# Sheet1.net
KiCad netlist of a schematic drawn in Altium Designer
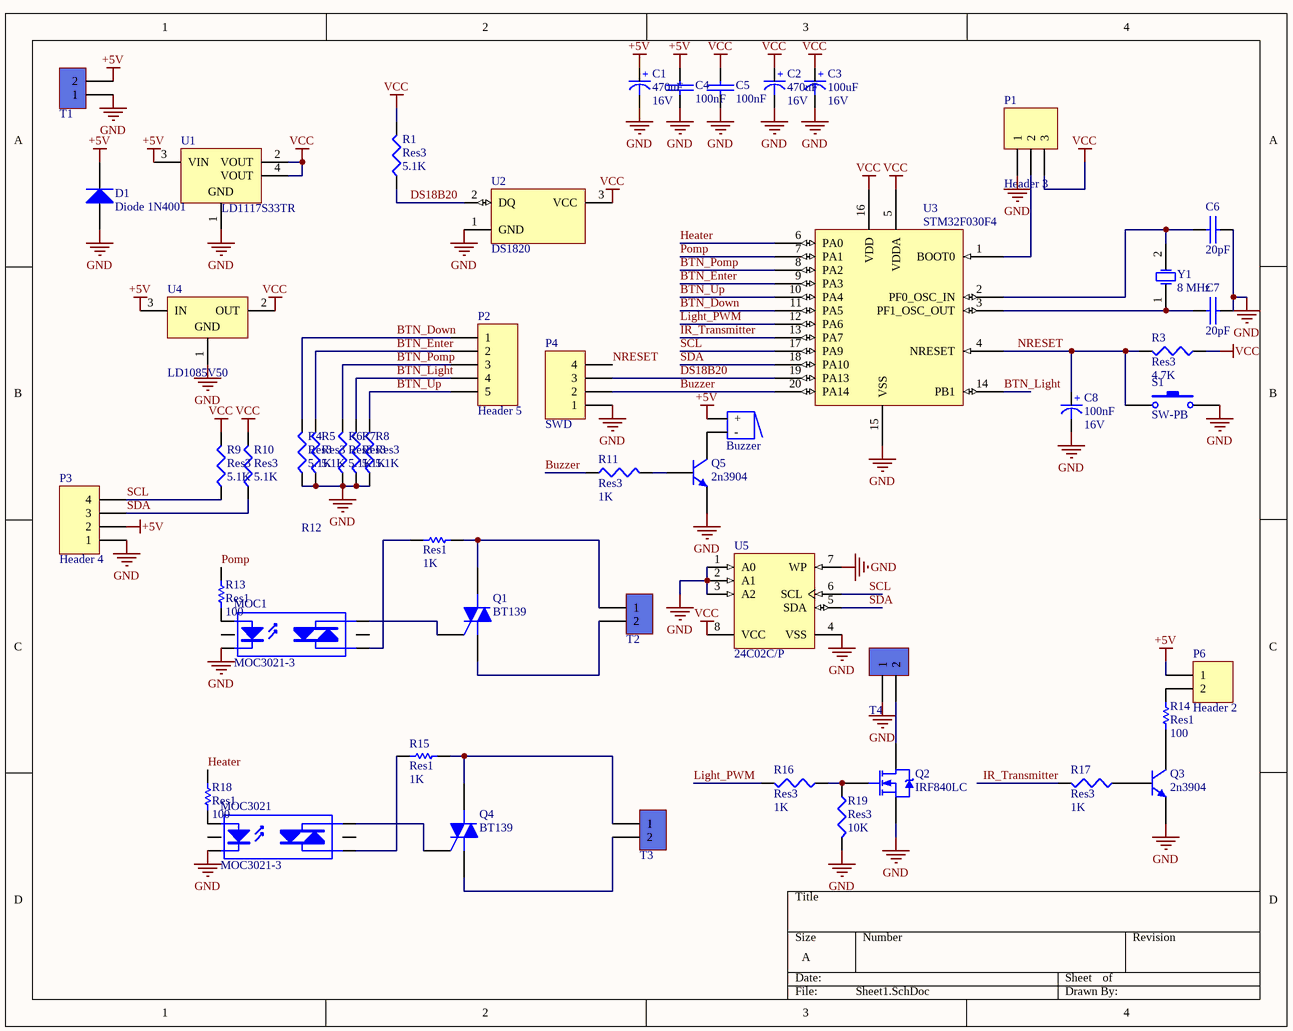
[diagram p0: Sheet1.SchDoc]

(export (version "E")
  (design (tool "Eeschema 10.0.6"))
  (components
    (comp (ref "Buzzer")
      (value "Buzzer")
      (footprint "BUZZER")
      (fields (field (name "DESIGNER") "Seyed Mohsen Ghasemain"))
      (libsource (lib "PicPars.com_usefully_Library") (part "Buzzer"))
    )
    (comp (ref "C1")
      (value "470uF")
      (footprint "cap 03")
      (description "Polar Capacitor")
      (fields (field (name "VOLTAGE") "16V") (field (name "DESIGNER") "Saeid Jorablo"))
      (libsource (lib "My_Library") (part "Cap-Polar"))
    )
    (comp (ref "C2")
      (value "470uF")
      (footprint "cap 03")
      (description "Polar Capacitor")
      (fields (field (name "VOLTAGE") "16V") (field (name "DESIGNER") "Saeid Jorablo"))
      (libsource (lib "My_Library") (part "Cap-Polar"))
    )
    (comp (ref "C3")
      (value "100uF")
      (footprint "cap 02")
      (description "Polar Capacitor")
      (fields (field (name "VOLTAGE") "16V") (field (name "DESIGNER") "Saeid Jorablo"))
      (libsource (lib "My_Library") (part "Cap-Polar"))
    )
    (comp (ref "C4")
      (value "100nF")
      (footprint "SMD_CAP_1206")
      (description "Bipolar Capacitor")
      (fields (field (name "VOLTAGE") "100V") (field (name "DESIGNER") "Saeid Jorablo"))
      (libsource (lib "My_Library") (part "Cap-Bipolar"))
    )
    (comp (ref "C5")
      (value "100nF")
      (footprint "SMD_CAP_1206")
      (description "Bipolar Capacitor")
      (fields (field (name "VOLTAGE") "100V") (field (name "DESIGNER") "Saeid Jorablo"))
      (libsource (lib "My_Library") (part "Cap-Bipolar"))
    )
    (comp (ref "C6")
      (value "20pF")
      (footprint "SMD_CAP_0603")
      (description "Bipolar Capacitor")
      (fields (field (name "VOLTAGE") "100V") (field (name "DESIGNER") "Saeid Jorablo"))
      (libsource (lib "My_Library") (part "Cap-Bipolar"))
    )
    (comp (ref "C7")
      (value "20pF")
      (footprint "SMD_CAP_0603")
      (description "Bipolar Capacitor")
      (fields (field (name "VOLTAGE") "100V") (field (name "DESIGNER") "Saeid Jorablo"))
      (libsource (lib "My_Library") (part "Cap-Bipolar"))
    )
    (comp (ref "C8")
      (value "100nF")
      (footprint "cap 01")
      (description "Polar Capacitor")
      (fields (field (name "VOLTAGE") "16V") (field (name "DESIGNER") "Saeid Jorablo"))
      (libsource (lib "My_Library") (part "Cap-Polar"))
    )
    (comp (ref "D1")
      (value "Diode 1N4001")
      (footprint "DO-41")
      (description "1 Amp General Purpose Rectifier")
      (fields (field (name "PUBLISHER") "Altium Limited"))
      (libsource (lib "Miscellaneous Devices") (part "Diode 1N4001"))
    )
    (comp (ref "MOC1")
      (value "MOC3021-3")
      (footprint "DIP-6")
      (description "Opto-Triac")
      (fields
        (field (name "PUBLISHER") "www.picpars.com")
        (field (name "DESIGNER") "Seyed Mohsen Ghasemian")
        (field (name "E-MAIL") "picpars@gmail.com")
      )
      (libsource (lib "usefully_Library") (part "MOC3021-3"))
    )
    (comp (ref "MOC3021")
      (value "MOC3021-3")
      (footprint "DIP-6")
      (description "Opto-Triac")
      (fields
        (field (name "PUBLISHER") "www.picpars.com")
        (field (name "DESIGNER") "Seyed Mohsen Ghasemian")
        (field (name "E-MAIL") "picpars@gmail.com")
      )
      (libsource (lib "usefully_Library") (part "MOC3021-3"))
    )
    (comp (ref "P1")
      (value "Header 3")
      (footprint "HDR1X3")
      (description "Header, 3-Pin")
      (fields (field (name "PUBLISHER") "Altium Limited"))
      (libsource (lib "Miscellaneous Connectors") (part "Header 3"))
    )
    (comp (ref "P2")
      (value "Header 5")
      (footprint "HDR1X5")
      (description "Header, 5-Pin")
      (fields (field (name "PUBLISHER") "Altium Limited"))
      (libsource (lib "Miscellaneous Connectors") (part "Header 5"))
    )
    (comp (ref "P3")
      (value "Header 4")
      (footprint "HDR1X4")
      (description "Header, 4-Pin")
      (fields (field (name "PUBLISHER") "Altium Limited"))
      (libsource (lib "Miscellaneous Connectors") (part "Header 4"))
    )
    (comp (ref "P4")
      (value "SWD")
      (footprint "HDR1X4")
      (description "Header, 4-Pin")
      (fields (field (name "PUBLISHER") "Altium Limited"))
      (libsource (lib "Miscellaneous Connectors") (part "Header 4"))
    )
    (comp (ref "P6")
      (value "Header 2")
      (footprint "HDR1X2")
      (description "Header, 2-Pin")
      (fields (field (name "PUBLISHER") "Altium Limited"))
      (libsource (lib "Devices") (part "Header 2"))
    )
    (comp (ref "Q1")
      (value "BT139")
      (footprint "221A-09")
      (description "Silicon Bidirectional Triode Thyristor")
      (fields (field (name "PUBLISHER") "Altium Limited"))
      (libsource (lib "Motorola Discrete TRIAC") (part "MAC15A6"))
    )
    (comp (ref "Q2")
      (value "IRF840LC")
      (footprint "TO-220AB")
      (description "HEXFET Power MOSFET")
      (fields (field (name "PUBLISHER") "Altium Limited"))
      (libsource (lib "IR Discrete MOSFET - Power") (part "IRF840LC"))
    )
    (comp (ref "Q3")
      (value "2n3904")
      (footprint "SOT323_L")
      (description "NPN Switching Transistor")
      (fields (field (name "PUBLISHER") "Altium Limited"))
      (libsource (lib "Philips Discrete BJT - Low Power") (part "PMST2222"))
    )
    (comp (ref "Q4")
      (value "BT139")
      (footprint "221A-09")
      (description "Silicon Bidirectional Triode Thyristor")
      (fields (field (name "PUBLISHER") "Altium Limited"))
      (libsource (lib "Motorola Discrete TRIAC") (part "MAC15A6"))
    )
    (comp (ref "Q5")
      (value "2n3904")
      (footprint "SOT323_L")
      (description "NPN Switching Transistor")
      (fields (field (name "PUBLISHER") "Altium Limited"))
      (libsource (lib "Philips Discrete BJT - Low Power") (part "PMST2222"))
    )
    (comp (ref "R1")
      (value "Res3")
      (footprint "J1-0603")
      (description "Resistor")
      (fields (field (name "ALTIUM_VALUE") "5.1K") (field (name "PUBLISHER") "Altium Limited"))
      (libsource (lib "Miscellaneous Devices") (part "Res3"))
    )
    (comp (ref "R3")
      (value "Res3")
      (footprint "J1-0603")
      (description "Resistor")
      (fields (field (name "ALTIUM_VALUE") "4.7K") (field (name "PUBLISHER") "Altium Limited"))
      (libsource (lib "Miscellaneous Devices") (part "Res3"))
    )
    (comp (ref "R4")
      (value "Res3")
      (footprint "J1-0603")
      (description "Resistor")
      (fields (field (name "ALTIUM_VALUE") "5.1K") (field (name "PUBLISHER") "Altium Limited"))
      (libsource (lib "Miscellaneous Devices") (part "Res3"))
    )
    (comp (ref "R5")
      (value "Res3")
      (footprint "J1-0603")
      (description "Resistor")
      (fields (field (name "ALTIUM_VALUE") "5.1K") (field (name "PUBLISHER") "Altium Limited"))
      (libsource (lib "Miscellaneous Devices") (part "Res3"))
    )
    (comp (ref "R6")
      (value "Res3")
      (footprint "J1-0603")
      (description "Resistor")
      (fields (field (name "ALTIUM_VALUE") "5.1K") (field (name "PUBLISHER") "Altium Limited"))
      (libsource (lib "Miscellaneous Devices") (part "Res3"))
    )
    (comp (ref "R7")
      (value "Res3")
      (footprint "J1-0603")
      (description "Resistor")
      (fields (field (name "ALTIUM_VALUE") "5.1K") (field (name "PUBLISHER") "Altium Limited"))
      (libsource (lib "Miscellaneous Devices") (part "Res3"))
    )
    (comp (ref "R8")
      (value "Res3")
      (footprint "J1-0603")
      (description "Resistor")
      (fields (field (name "ALTIUM_VALUE") "5.1K") (field (name "PUBLISHER") "Altium Limited"))
      (libsource (lib "Miscellaneous Devices") (part "Res3"))
    )
    (comp (ref "R9")
      (value "Res3")
      (footprint "J1-0603")
      (description "Resistor")
      (fields (field (name "ALTIUM_VALUE") "5.1K") (field (name "PUBLISHER") "Altium Limited"))
      (libsource (lib "Miscellaneous Devices") (part "Res3"))
    )
    (comp (ref "R10")
      (value "Res3")
      (footprint "J1-0603")
      (description "Resistor")
      (fields (field (name "ALTIUM_VALUE") "5.1K") (field (name "PUBLISHER") "Altium Limited"))
      (libsource (lib "Miscellaneous Devices") (part "Res3"))
    )
    (comp (ref "R11")
      (value "Res3")
      (footprint "AXIAL-0.3")
      (description "Resistor")
      (fields (field (name "ALTIUM_VALUE") "1K") (field (name "PUBLISHER") "Altium Limited"))
      (libsource (lib "Miscellaneous Devices") (part "Res3"))
    )
    (comp (ref "R12")
      (value "Res1")
      (footprint "AXIAL-0.3")
      (description "Resistor")
      (fields (field (name "ALTIUM_VALUE") "1K") (field (name "PUBLISHER") "Altium Limited"))
      (libsource (lib "Miscellaneous Devices") (part "Res1"))
    )
    (comp (ref "R13")
      (value "Res1")
      (footprint "AXIAL-0.3")
      (description "Resistor")
      (fields (field (name "ALTIUM_VALUE") "100") (field (name "PUBLISHER") "Altium Limited"))
      (libsource (lib "Miscellaneous Devices") (part "Res1"))
    )
    (comp (ref "R14")
      (value "Res1")
      (footprint "AXIAL-0.3")
      (description "Resistor")
      (fields (field (name "ALTIUM_VALUE") "100") (field (name "PUBLISHER") "Altium Limited"))
      (libsource (lib "Miscellaneous Devices") (part "Res1"))
    )
    (comp (ref "R15")
      (value "Res1")
      (footprint "AXIAL-0.3")
      (description "Resistor")
      (fields (field (name "ALTIUM_VALUE") "1K") (field (name "PUBLISHER") "Altium Limited"))
      (libsource (lib "Miscellaneous Devices") (part "Res1"))
    )
    (comp (ref "R16")
      (value "Res3")
      (footprint "J1-0603")
      (description "Resistor")
      (fields (field (name "ALTIUM_VALUE") "1K") (field (name "PUBLISHER") "Altium Limited"))
      (libsource (lib "Miscellaneous Devices") (part "Res3"))
    )
    (comp (ref "R17")
      (value "Res3")
      (footprint "J1-0603")
      (description "Resistor")
      (fields (field (name "ALTIUM_VALUE") "1K") (field (name "PUBLISHER") "Altium Limited"))
      (libsource (lib "Miscellaneous Devices") (part "Res3"))
    )
    (comp (ref "R18")
      (value "Res1")
      (footprint "AXIAL-0.3")
      (description "Resistor")
      (fields (field (name "ALTIUM_VALUE") "100") (field (name "PUBLISHER") "Altium Limited"))
      (libsource (lib "Miscellaneous Devices") (part "Res1"))
    )
    (comp (ref "R19")
      (value "Res3")
      (footprint "J1-0603")
      (description "Resistor")
      (fields (field (name "ALTIUM_VALUE") "10K") (field (name "PUBLISHER") "Altium Limited"))
      (libsource (lib "Miscellaneous Devices") (part "Res3"))
    )
    (comp (ref "S1")
      (value "SW-PB")
      (footprint "SPST-2")
      (description "Switch")
      (fields (field (name "PUBLISHER") "Altium Limited"))
      (libsource (lib "Miscellaneous Devices") (part "SW-PB"))
    )
    (comp (ref "T1")
      (value "Terminal")
      (footprint "Terminal 1*2")
      (description "Terminal 2 Pin 250VAC 16A")
      (fields (field (name "DESIGNER") "Seyed Mohsen Ghasemain") (field (name "E-MAIL") "picpars@gmail.com"))
      (libsource (lib "PicPars.com_usefully_Library") (part "Terminal 1*2"))
    )
    (comp (ref "T2")
      (value "Terminal")
      (footprint "Terminal 1*2")
      (description "Terminal 2 Pin 250VAC 16A")
      (fields (field (name "DESIGNER") "Seyed Mohsen Ghasemain") (field (name "E-MAIL") "picpars@gmail.com"))
      (libsource (lib "") (part "Terminal 1*2_2"))
    )
    (comp (ref "T3")
      (value "Terminal")
      (footprint "Terminal 1*2")
      (description "Terminal 2 Pin 250VAC 16A")
      (fields (field (name "DESIGNER") "Seyed Mohsen Ghasemain") (field (name "E-MAIL") "picpars@gmail.com"))
      (libsource (lib "") (part "Terminal 1*2_2"))
    )
    (comp (ref "T4")
      (value "Terminal")
      (footprint "Terminal 1*2")
      (description "Terminal 2 Pin 250VAC 16A")
      (fields (field (name "DESIGNER") "Seyed Mohsen Ghasemain") (field (name "E-MAIL") "picpars@gmail.com"))
      (libsource (lib "") (part "Terminal 1*2_1"))
    )
    (comp (ref "U1")
      (value "LD1117S33TR")
      (footprint "SOT-223_N")
      (description "Fixed Low Drop Positive Voltage Regulator, 3.3V, 4-Pin SOT-223, Tape and Reel")
      (libsource (lib "STMicroelectronics Power Management Linear Regulator") (part "LD1117S33TR"))
    )
    (comp (ref "U2")
      (value "DS1820")
      (footprint "HDR1X3")
      (description "1-Wire Digital Thermometer")
      (fields (field (name "PUBLISHER") "Altium Limited"))
      (libsource (lib "PicPars.com_usefully_Library") (part "DS1820"))
    )
    (comp (ref "U3")
      (value "STM32F030F4")
      (footprint "TSSOP20")
      (description "STM32 ARM-based 32-bit MCU")
      (libsource (lib "Amir") (part "STM32F030F4"))
    )
    (comp (ref "U4")
      (value "LD1085V50")
      (footprint "TO220")
      (description "3A, Low Drop Positive Voltage Regulator, 5V, 3-Pin TO-220")
      (libsource (lib "STMicroelectronics Power Management Linear Regulator") (part "LD1085V50"))
    )
    (comp (ref "U5")
      (value "24C02C/P")
      (footprint "PDIP300-P8")
      (description "2Kbit, 400kHz, 5V, I2C Serial EEPROM, 8-Pin PDIP, Commercial Temperature")
      (fields (field (name "PUBLISHER") "Altium Limited"))
      (libsource (lib "Microchip EEPROM I2C Serial") (part "24C02C/P"))
    )
    (comp (ref "Y1")
      (value "8 MHz")
      (footprint "XTAL")
      (description "XTAL Crystal")
      (libsource (lib "My_Library") (part "XTAL"))
    )
  )
  (nets
    (net (code "1") (name "+5V") (class "Default")
      (node (ref "Buzzer") (pin "1") (pinfunction "+_1") (pintype "passive"))
      (node (ref "C1") (pin "1") (pinfunction "+_1") (pintype "passive"))
      (node (ref "C4") (pin "1") (pinfunction "+_1") (pintype "passive"))
      (node (ref "D1") (pin "2") (pinfunction "K_2") (pintype "passive"))
      (node (ref "P3") (pin "2") (pinfunction "2_2") (pintype "passive"))
      (node (ref "P6") (pin "1") (pinfunction "1_1") (pintype "passive"))
      (node (ref "T1") (pin "2") (pinfunction "2_2") (pintype "passive"))
      (node (ref "U1") (pin "3") (pinfunction "VIN_3") (pintype "power_in"))
      (node (ref "U4") (pin "3") (pinfunction "IN_3") (pintype "power_in"))
    )
    (net (code "2") (name "/BTN_Down") (class "Default")
      (node (ref "P2") (pin "1") (pinfunction "1_1") (pintype "passive"))
      (node (ref "R4") (pin "2") (pinfunction "2_2") (pintype "passive"))
      (node (ref "U3") (pin "11") (pinfunction "PA5_11") (pintype "bidirectional"))
    )
    (net (code "3") (name "/BTN_Enter") (class "Default")
      (node (ref "P2") (pin "2") (pinfunction "2_2") (pintype "passive"))
      (node (ref "R5") (pin "2") (pinfunction "2_2") (pintype "passive"))
      (node (ref "U3") (pin "9") (pinfunction "PA3_9") (pintype "bidirectional"))
    )
    (net (code "4") (name "/BTN_Light") (class "Default")
      (node (ref "P2") (pin "4") (pinfunction "4_4") (pintype "passive"))
      (node (ref "R7") (pin "2") (pinfunction "2_2") (pintype "passive"))
      (node (ref "U3") (pin "14") (pinfunction "PB1_14") (pintype "bidirectional"))
    )
    (net (code "5") (name "/BTN_Pomp") (class "Default")
      (node (ref "P2") (pin "3") (pinfunction "3_3") (pintype "passive"))
      (node (ref "R6") (pin "2") (pinfunction "2_2") (pintype "passive"))
      (node (ref "U3") (pin "8") (pinfunction "PA2_8") (pintype "bidirectional"))
    )
    (net (code "6") (name "/BTN_Up") (class "Default")
      (node (ref "P2") (pin "5") (pinfunction "5_5") (pintype "passive"))
      (node (ref "R8") (pin "2") (pinfunction "2_2") (pintype "passive"))
      (node (ref "U3") (pin "10") (pinfunction "PA4_10") (pintype "bidirectional"))
    )
    (net (code "7") (name "/Buzzer") (class "Default")
      (node (ref "P4") (pin "2") (pinfunction "2_2") (pintype "passive"))
      (node (ref "R11") (pin "1") (pinfunction "1_1") (pintype "passive"))
      (node (ref "U3") (pin "20") (pinfunction "PA14_20") (pintype "bidirectional"))
    )
    (net (code "8") (name "/DS18B20") (class "Default")
      (node (ref "P4") (pin "3") (pinfunction "3_3") (pintype "passive"))
      (node (ref "R1") (pin "1") (pinfunction "1_1") (pintype "passive"))
      (node (ref "U2") (pin "2") (pinfunction "DQ_2") (pintype "bidirectional"))
      (node (ref "U3") (pin "19") (pinfunction "PA13_19") (pintype "bidirectional"))
    )
    (net (code "9") (name "/Heater") (class "Default")
      (node (ref "R18") (pin "1") (pinfunction "1_1") (pintype "passive"))
      (node (ref "U3") (pin "6") (pinfunction "PA0_6") (pintype "bidirectional"))
    )
    (net (code "10") (name "/IR_Transmitter") (class "Default")
      (node (ref "R17") (pin "2") (pinfunction "2_2") (pintype "passive"))
      (node (ref "U3") (pin "13") (pinfunction "PA7_13") (pintype "bidirectional"))
    )
    (net (code "11") (name "/Light_PWM") (class "Default")
      (node (ref "R16") (pin "2") (pinfunction "2_2") (pintype "passive"))
      (node (ref "U3") (pin "12") (pinfunction "PA6_12") (pintype "bidirectional"))
    )
    (net (code "12") (name "/NRESET") (class "Default")
      (node (ref "C8") (pin "1") (pinfunction "+_1") (pintype "passive"))
      (node (ref "P4") (pin "4") (pinfunction "4_4") (pintype "passive"))
      (node (ref "R3") (pin "2") (pinfunction "2_2") (pintype "passive"))
      (node (ref "S1") (pin "1") (pinfunction "1_1") (pintype "passive"))
      (node (ref "U3") (pin "4") (pinfunction "NRESET_4") (pintype "input"))
    )
    (net (code "13") (name "/Pomp") (class "Default")
      (node (ref "R13") (pin "1") (pinfunction "1_1") (pintype "passive"))
      (node (ref "U3") (pin "7") (pinfunction "PA1_7") (pintype "bidirectional"))
    )
    (net (code "14") (name "/SCL") (class "Default")
      (node (ref "P3") (pin "4") (pinfunction "4_4") (pintype "passive"))
      (node (ref "R9") (pin "1") (pinfunction "1_1") (pintype "passive"))
      (node (ref "U3") (pin "17") (pinfunction "PA9_17") (pintype "bidirectional"))
      (node (ref "U5") (pin "6") (pinfunction "SCL_6") (pintype "input"))
    )
    (net (code "15") (name "/SDA") (class "Default")
      (node (ref "P3") (pin "3") (pinfunction "3_3") (pintype "passive"))
      (node (ref "R10") (pin "1") (pinfunction "1_1") (pintype "passive"))
      (node (ref "U3") (pin "18") (pinfunction "PA10_18") (pintype "bidirectional"))
      (node (ref "U5") (pin "5") (pinfunction "SDA_5") (pintype "bidirectional"))
    )
    (net (code "16") (name "GND") (class "Default")
      (node (ref "C1") (pin "2") (pinfunction "-_2") (pintype "passive"))
      (node (ref "C2") (pin "2") (pinfunction "-_2") (pintype "passive"))
      (node (ref "C3") (pin "2") (pinfunction "-_2") (pintype "passive"))
      (node (ref "C4") (pin "2") (pinfunction "-_2") (pintype "passive"))
      (node (ref "C5") (pin "2") (pinfunction "-_2") (pintype "passive"))
      (node (ref "C6") (pin "2") (pinfunction "-_2") (pintype "passive"))
      (node (ref "C7") (pin "2") (pinfunction "-_2") (pintype "passive"))
      (node (ref "C8") (pin "2") (pinfunction "-_2") (pintype "passive"))
      (node (ref "D1") (pin "1") (pinfunction "A_1") (pintype "passive"))
      (node (ref "MOC1") (pin "2") (pinfunction "K_2") (pintype "passive"))
      (node (ref "MOC3021") (pin "2") (pinfunction "K_2") (pintype "passive"))
      (node (ref "P1") (pin "1") (pinfunction "1_1") (pintype "passive"))
      (node (ref "P3") (pin "1") (pinfunction "1_1") (pintype "passive"))
      (node (ref "P4") (pin "1") (pinfunction "1_1") (pintype "passive"))
      (node (ref "Q2") (pin "3") (pinfunction "S_3") (pintype "passive"))
      (node (ref "Q3") (pin "2") (pinfunction "E_2") (pintype "passive"))
      (node (ref "Q5") (pin "2") (pinfunction "E_2") (pintype "passive"))
      (node (ref "R19") (pin "2") (pinfunction "2_2") (pintype "passive"))
      (node (ref "R4") (pin "1") (pinfunction "1_1") (pintype "passive"))
      (node (ref "R5") (pin "1") (pinfunction "1_1") (pintype "passive"))
      (node (ref "R6") (pin "1") (pinfunction "1_1") (pintype "passive"))
      (node (ref "R7") (pin "1") (pinfunction "1_1") (pintype "passive"))
      (node (ref "R8") (pin "1") (pinfunction "1_1") (pintype "passive"))
      (node (ref "S1") (pin "2") (pinfunction "2_2") (pintype "passive"))
      (node (ref "T1") (pin "1") (pinfunction "1_1") (pintype "passive"))
      (node (ref "T4") (pin "1") (pinfunction "1_1") (pintype "passive"))
      (node (ref "U1") (pin "1") (pinfunction "GND_1") (pintype "power_in"))
      (node (ref "U2") (pin "1") (pinfunction "GND_1") (pintype "power_in"))
      (node (ref "U3") (pin "15") (pinfunction "VSS_15") (pintype "power_in"))
      (node (ref "U4") (pin "1") (pinfunction "GND_1") (pintype "power_in"))
      (node (ref "U5") (pin "1") (pinfunction "A0_1") (pintype "input"))
      (node (ref "U5") (pin "2") (pinfunction "A1_2") (pintype "input"))
      (node (ref "U5") (pin "3") (pinfunction "A2_3") (pintype "input"))
      (node (ref "U5") (pin "4") (pinfunction "VSS_4") (pintype "power_in"))
      (node (ref "U5") (pin "7") (pinfunction "WP_7") (pintype "input"))
    )
    (net (code "17") (name "Net-(Buzzer--)") (class "Default")
      (node (ref "Buzzer") (pin "2") (pinfunction "-_2") (pintype "passive"))
      (node (ref "Q5") (pin "3") (pinfunction "C_3") (pintype "passive"))
    )
    (net (code "18") (name "Net-(C6-+)") (class "Default")
      (node (ref "C6") (pin "1") (pinfunction "+_1") (pintype "passive"))
      (node (ref "U3") (pin "2") (pinfunction "PF0_OSC_IN_2") (pintype "bidirectional"))
      (node (ref "Y1") (pin "2") (pinfunction "OSC2_2") (pintype "passive"))
    )
    (net (code "19") (name "Net-(C7-+)") (class "Default")
      (node (ref "C7") (pin "1") (pinfunction "+_1") (pintype "passive"))
      (node (ref "U3") (pin "3") (pinfunction "PF1_OSC_OUT_3") (pintype "bidirectional"))
      (node (ref "Y1") (pin "1") (pinfunction "OSC1_1") (pintype "passive"))
    )
    (net (code "20") (name "Net-(MOC1-A)") (class "Default")
      (node (ref "MOC1") (pin "1") (pinfunction "A_1") (pintype "passive"))
      (node (ref "R13") (pin "2") (pinfunction "2_2") (pintype "passive"))
    )
    (net (code "21") (name "Net-(MOC1-A{slash}K-Pad6)") (class "Default")
      (node (ref "MOC1") (pin "6") (pinfunction "A/K_6") (pintype "passive"))
      (node (ref "R12") (pin "1") (pinfunction "1_1") (pintype "passive"))
    )
    (net (code "22") (name "Net-(MOC3021-A)") (class "Default")
      (node (ref "MOC3021") (pin "1") (pinfunction "A_1") (pintype "passive"))
      (node (ref "R18") (pin "2") (pinfunction "2_2") (pintype "passive"))
    )
    (net (code "23") (name "Net-(MOC3021-A{slash}K-Pad6)") (class "Default")
      (node (ref "MOC3021") (pin "6") (pinfunction "A/K_6") (pintype "passive"))
      (node (ref "R15") (pin "1") (pinfunction "1_1") (pintype "passive"))
    )
    (net (code "24") (name "Net-(P6-Pad2)") (class "Default")
      (node (ref "P6") (pin "2") (pinfunction "2_2") (pintype "passive"))
      (node (ref "R14") (pin "1") (pinfunction "1_1") (pintype "passive"))
    )
    (net (code "25") (name "Net-(Q1-G)") (class "Default")
      (node (ref "MOC1") (pin "4") (pinfunction "A/K_4") (pintype "passive"))
      (node (ref "Q1") (pin "3") (pinfunction "G_3") (pintype "passive"))
    )
    (net (code "26") (name "Net-(Q1-M1)") (class "Default")
      (node (ref "Q1") (pin "1") (pinfunction "M1_1") (pintype "passive"))
      (node (ref "T2") (pin "2") (pinfunction "2_2") (pintype "passive"))
    )
    (net (code "27") (name "Net-(Q1-M2)") (class "Default")
      (node (ref "Q1") (pin "2") (pinfunction "M2_2") (pintype "passive"))
      (node (ref "R12") (pin "2") (pinfunction "2_2") (pintype "passive"))
      (node (ref "T2") (pin "1") (pinfunction "1_1") (pintype "passive"))
    )
    (net (code "28") (name "Net-(Q2-D)") (class "Default")
      (node (ref "Q2") (pin "2") (pinfunction "D_2") (pintype "passive"))
      (node (ref "T4") (pin "2") (pinfunction "2_2") (pintype "passive"))
    )
    (net (code "29") (name "Net-(Q2-G)") (class "Default")
      (node (ref "Q2") (pin "1") (pinfunction "G_1") (pintype "passive"))
      (node (ref "R16") (pin "1") (pinfunction "1_1") (pintype "passive"))
      (node (ref "R19") (pin "1") (pinfunction "1_1") (pintype "passive"))
    )
    (net (code "30") (name "Net-(Q3-B)") (class "Default")
      (node (ref "Q3") (pin "1") (pinfunction "B_1") (pintype "passive"))
      (node (ref "R17") (pin "1") (pinfunction "1_1") (pintype "passive"))
    )
    (net (code "31") (name "Net-(Q3-C)") (class "Default")
      (node (ref "Q3") (pin "3") (pinfunction "C_3") (pintype "passive"))
      (node (ref "R14") (pin "2") (pinfunction "2_2") (pintype "passive"))
    )
    (net (code "32") (name "Net-(Q4-G)") (class "Default")
      (node (ref "MOC3021") (pin "4") (pinfunction "A/K_4") (pintype "passive"))
      (node (ref "Q4") (pin "3") (pinfunction "G_3") (pintype "passive"))
    )
    (net (code "33") (name "Net-(Q4-M1)") (class "Default")
      (node (ref "Q4") (pin "1") (pinfunction "M1_1") (pintype "passive"))
      (node (ref "T3") (pin "2") (pinfunction "2_2") (pintype "passive"))
    )
    (net (code "34") (name "Net-(Q4-M2)") (class "Default")
      (node (ref "Q4") (pin "2") (pinfunction "M2_2") (pintype "passive"))
      (node (ref "R15") (pin "2") (pinfunction "2_2") (pintype "passive"))
      (node (ref "T3") (pin "1") (pinfunction "1_1") (pintype "passive"))
    )
    (net (code "35") (name "Net-(Q5-B)") (class "Default")
      (node (ref "Q5") (pin "1") (pinfunction "B_1") (pintype "passive"))
      (node (ref "R11") (pin "2") (pinfunction "2_2") (pintype "passive"))
    )
    (net (code "36") (name "Net-(U3-BOOT0)") (class "Default")
      (node (ref "P1") (pin "2") (pinfunction "2_2") (pintype "passive"))
      (node (ref "U3") (pin "1") (pinfunction "BOOT0_1") (pintype "input"))
    )
    (net (code "37") (name "VCC") (class "Default")
      (node (ref "C2") (pin "1") (pinfunction "+_1") (pintype "passive"))
      (node (ref "C3") (pin "1") (pinfunction "+_1") (pintype "passive"))
      (node (ref "C5") (pin "1") (pinfunction "+_1") (pintype "passive"))
      (node (ref "P1") (pin "3") (pinfunction "3_3") (pintype "passive"))
      (node (ref "R1") (pin "2") (pinfunction "2_2") (pintype "passive"))
      (node (ref "R10") (pin "2") (pinfunction "2_2") (pintype "passive"))
      (node (ref "R3") (pin "1") (pinfunction "1_1") (pintype "passive"))
      (node (ref "R9") (pin "2") (pinfunction "2_2") (pintype "passive"))
      (node (ref "U1") (pin "2") (pinfunction "VOUT_2") (pintype "power_in"))
      (node (ref "U1") (pin "4") (pinfunction "VOUT_4") (pintype "power_in"))
      (node (ref "U2") (pin "3") (pinfunction "VCC_3") (pintype "power_in"))
      (node (ref "U3") (pin "16") (pinfunction "VDD_16") (pintype "power_in"))
      (node (ref "U3") (pin "5") (pinfunction "VDDA_5") (pintype "power_in"))
      (node (ref "U4") (pin "2") (pinfunction "OUT_2") (pintype "power_in"))
      (node (ref "U5") (pin "8") (pinfunction "VCC_8") (pintype "power_in"))
    )
    (net (code "38") (name "unconnected-(MOC1-NC-Pad3)") (class "Default")
      (node (ref "MOC1") (pin "3") (pinfunction "NC_3") (pintype "passive"))
    )
    (net (code "39") (name "unconnected-(MOC1-NC-Pad5)") (class "Default")
      (node (ref "MOC1") (pin "5") (pinfunction "NC_5") (pintype "passive"))
    )
    (net (code "40") (name "unconnected-(MOC3021-NC-Pad3)") (class "Default")
      (node (ref "MOC3021") (pin "3") (pinfunction "NC_3") (pintype "passive"))
    )
    (net (code "41") (name "unconnected-(MOC3021-NC-Pad5)") (class "Default")
      (node (ref "MOC3021") (pin "5") (pinfunction "NC_5") (pintype "passive"))
    )
  )
)
